# Headphone_Amp.net
KiCad netlist of a schematic drawn in EAGLE
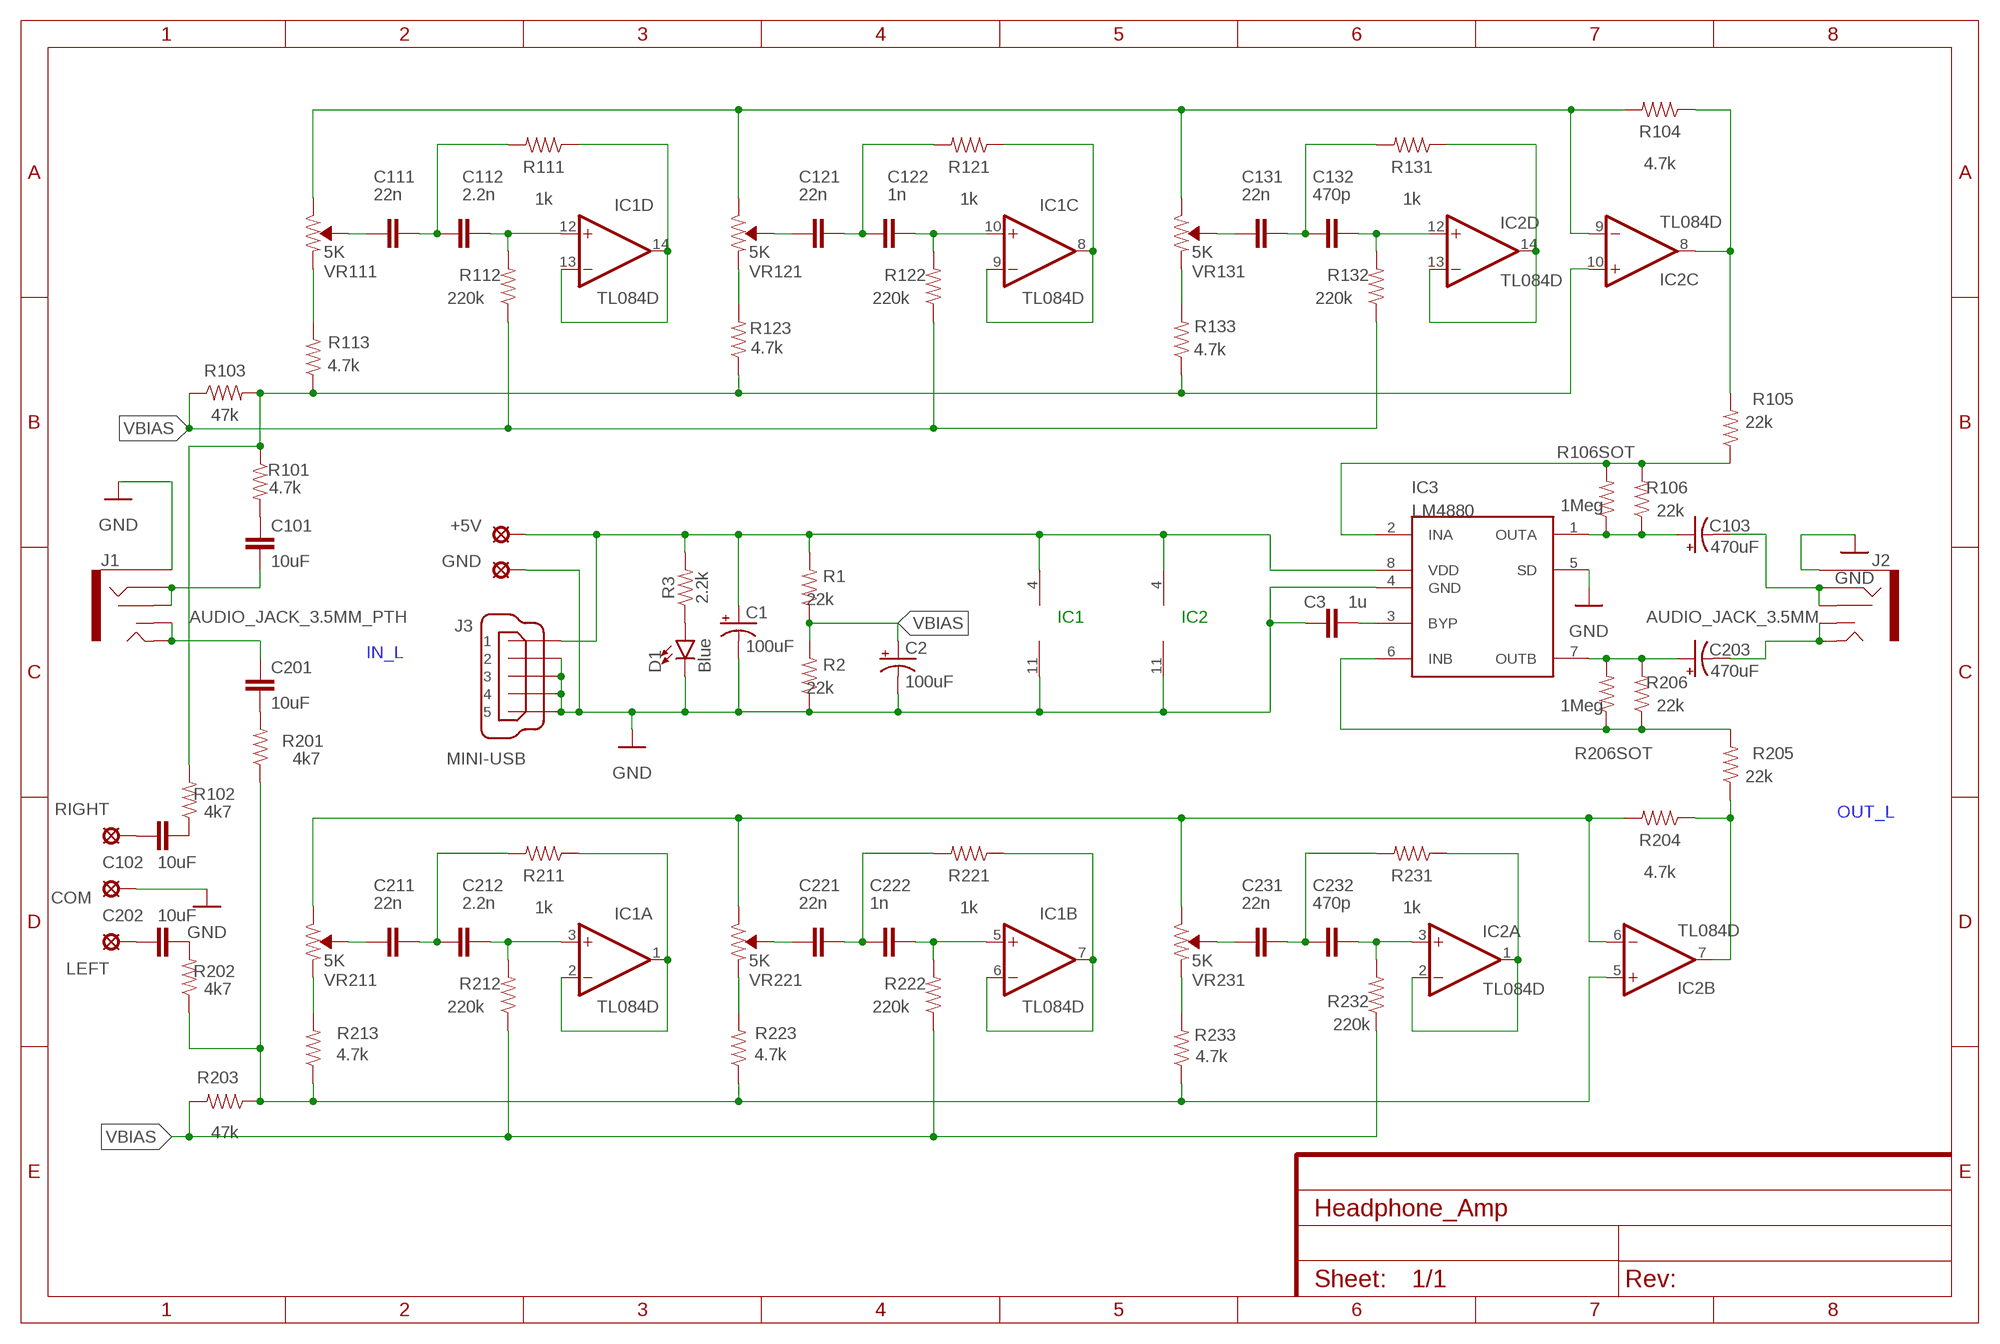
[diagram p0: schematic, sheet 1]

(export (version "E")
  (design (tool "Eeschema 10.0.6"))
  (components
    (comp (ref "+5V")
      (value "SE14")
      (footprint "eagle-import:SE14")
      (fields (field (name "SPICEMODEL") "PwrPlus") (field (name "SPICEPREFIX") "X"))
      (libsource (lib "eagle-import") (part "SE14"))
    )
    (comp (ref "C1")
      (value "100uF")
      (footprint "eagle-import:EIA7343")
      (fields (field (name "SPICEPREFIX") "C"))
      (libsource (lib "eagle-import") (part "100UF-POLAR-EIA7343-16V-10%(TANT)"))
    )
    (comp (ref "C2")
      (value "100uF")
      (footprint "eagle-import:EIA7343")
      (fields (field (name "SPICEPREFIX") "C"))
      (libsource (lib "eagle-import") (part "100UF-POLAR-EIA7343-16V-10%(TANT)"))
    )
    (comp (ref "C3")
      (value "1u")
      (footprint "eagle-import:0603")
      (fields (field (name "SPICEPREFIX") "C"))
      (libsource (lib "eagle-import") (part "0.1UF-0603-25V-5%"))
    )
    (comp (ref "C101")
      (value "10uF")
      (footprint "eagle-import:0805")
      (fields (field (name "SPICEPREFIX") "C"))
      (libsource (lib "eagle-import") (part "10UF-0805-10V-10%"))
    )
    (comp (ref "C102")
      (value "10uF")
      (footprint "eagle-import:0805")
      (fields (field (name "SPICEPREFIX") "C"))
      (libsource (lib "eagle-import") (part "10UF-0805-10V-10%"))
    )
    (comp (ref "C103")
      (value "470uF")
      (footprint "eagle-import:EIA7343")
      (fields (field (name "SPICEPREFIX") "C"))
      (libsource (lib "eagle-import") (part "100UF-POLAR-EIA7343-16V-10%(TANT)"))
    )
    (comp (ref "C111")
      (value "22n")
      (footprint "eagle-import:0603")
      (fields (field (name "SPICEPREFIX") "C"))
      (libsource (lib "eagle-import") (part "0.1UF-0603-25V-5%"))
    )
    (comp (ref "C112")
      (value "2.2n")
      (footprint "eagle-import:0603")
      (fields (field (name "SPICEPREFIX") "C"))
      (libsource (lib "eagle-import") (part "0.1UF-0603-25V-5%"))
    )
    (comp (ref "C121")
      (value "22n")
      (footprint "eagle-import:0603")
      (fields (field (name "SPICEPREFIX") "C"))
      (libsource (lib "eagle-import") (part "0.1UF-0603-25V-5%"))
    )
    (comp (ref "C122")
      (value "1n")
      (footprint "eagle-import:0603")
      (fields (field (name "SPICEPREFIX") "C"))
      (libsource (lib "eagle-import") (part "0.1UF-0603-25V-5%"))
    )
    (comp (ref "C131")
      (value "22n")
      (footprint "eagle-import:0603")
      (fields (field (name "SPICEPREFIX") "C"))
      (libsource (lib "eagle-import") (part "0.1UF-0603-25V-5%"))
    )
    (comp (ref "C132")
      (value "470p")
      (footprint "eagle-import:0603")
      (fields (field (name "SPICEPREFIX") "C"))
      (libsource (lib "eagle-import") (part "0.1UF-0603-25V-5%"))
    )
    (comp (ref "C201")
      (value "10uF")
      (footprint "eagle-import:0805")
      (fields (field (name "SPICEPREFIX") "C"))
      (libsource (lib "eagle-import") (part "10UF-0805-10V-10%"))
    )
    (comp (ref "C202")
      (value "10uF")
      (footprint "eagle-import:0805")
      (fields (field (name "SPICEPREFIX") "C"))
      (libsource (lib "eagle-import") (part "10UF-0805-10V-10%"))
    )
    (comp (ref "C203")
      (value "470uF")
      (footprint "eagle-import:EIA7343")
      (fields (field (name "SPICEPREFIX") "C"))
      (libsource (lib "eagle-import") (part "100UF-POLAR-EIA7343-16V-10%(TANT)"))
    )
    (comp (ref "C211")
      (value "22n")
      (footprint "eagle-import:0603")
      (fields (field (name "SPICEPREFIX") "C"))
      (libsource (lib "eagle-import") (part "0.1UF-0603-25V-5%"))
    )
    (comp (ref "C212")
      (value "2.2n")
      (footprint "eagle-import:0603")
      (fields (field (name "SPICEPREFIX") "C"))
      (libsource (lib "eagle-import") (part "0.1UF-0603-25V-5%"))
    )
    (comp (ref "C221")
      (value "22n")
      (footprint "eagle-import:0603")
      (fields (field (name "SPICEPREFIX") "C"))
      (libsource (lib "eagle-import") (part "0.1UF-0603-25V-5%"))
    )
    (comp (ref "C222")
      (value "1n")
      (footprint "eagle-import:0603")
      (fields (field (name "SPICEPREFIX") "C"))
      (libsource (lib "eagle-import") (part "0.1UF-0603-25V-5%"))
    )
    (comp (ref "C231")
      (value "22n")
      (footprint "eagle-import:0603")
      (fields (field (name "SPICEPREFIX") "C"))
      (libsource (lib "eagle-import") (part "0.1UF-0603-25V-5%"))
    )
    (comp (ref "C232")
      (value "470p")
      (footprint "eagle-import:0603")
      (fields (field (name "SPICEPREFIX") "C"))
      (libsource (lib "eagle-import") (part "0.1UF-0603-25V-5%"))
    )
    (comp (ref "COM")
      (value "SE14")
      (footprint "eagle-import:SE14")
      (fields (field (name "SPICEMODEL") "PwrMinus") (field (name "SPICEPREFIX") "X"))
      (libsource (lib "eagle-import") (part "SE14"))
    )
    (comp (ref "D1")
      (value "Blue")
      (footprint "eagle-import:LED_3MM")
      (fields (field (name "SPICEMODEL") "DMOD") (field (name "SPICEPREFIX") "D"))
      (libsource (lib "eagle-import") (part "LED3MM"))
    )
    (comp (ref "GND")
      (value "SE14")
      (footprint "eagle-import:SE14")
      (fields (field (name "SPICEMODEL") "PwrMinus") (field (name "SPICEPREFIX") "X"))
      (libsource (lib "eagle-import") (part "SE14"))
    )
    (comp (ref "IC1")
      (value "TL084D")
      (footprint "eagle-import:SO14")
      (fields (field (name "SPICEMODEL") "TL084x4") (field (name "SPICEPREFIX") "X"))
      (libsource (lib "eagle-import") (part "TL084D"))
    )
    (comp (ref "IC2")
      (value "TL084D")
      (footprint "eagle-import:SO14")
      (fields (field (name "SPICEMODEL") "TL084x4") (field (name "SPICEPREFIX") "X"))
      (libsource (lib "eagle-import") (part "TL084D"))
    )
    (comp (ref "IC3")
      (value "LM4880")
      (footprint "eagle-import:SO08")
      (fields
        (field (name "MF") "Texas Instruments")
        (field (name "SPICEMODEL") "Fake_LM4880")
        (field (name "SPICEPREFIX") "X")
      )
      (libsource (lib "eagle-import") (part "LM4880"))
    )
    (comp (ref "J1")
      (value "AUDIO_JACK_3.5MM_PTH")
      (footprint "eagle-import:AUDIO-JACK")
      (fields (field (name "SPICEMODEL") "StereoIn") (field (name "SPICEPREFIX") "X"))
      (libsource (lib "eagle-import") (part "AUDIO_JACK_3.5MM_PTH"))
    )
    (comp (ref "J2")
      (value "AUDIO_JACK_3.5MM")
      (footprint "eagle-import:AUDIO-JACK")
      (fields (field (name "SPICEMODEL") "StereoOut") (field (name "SPICEPREFIX") "X"))
      (libsource (lib "eagle-import") (part "AUDIO_JACK_3.5MM_PTH"))
    )
    (comp (ref "J3")
      (value "MINI-USB")
      (footprint "eagle-import:UX60A-MB-5ST")
      (fields (field (name "SPICEMODEL") "USBSupply") (field (name "SPICEPREFIX") "X"))
      (libsource (lib "eagle-import") (part "MINI-USB-UX60A-MB-5ST"))
    )
    (comp (ref "LEFT")
      (value "SE14")
      (footprint "eagle-import:SE14")
      (fields (field (name "SPICEMODEL") "AudioIn") (field (name "SPICEPREFIX") "X"))
      (libsource (lib "eagle-import") (part "SE14"))
    )
    (comp (ref "R1")
      (value "22k")
      (footprint "eagle-import:0603")
      (fields (field (name "SPICEPREFIX") "R"))
      (libsource (lib "eagle-import") (part "RESISTOR0603"))
    )
    (comp (ref "R2")
      (value "22k")
      (footprint "eagle-import:0603")
      (fields (field (name "SPICEPREFIX") "R"))
      (libsource (lib "eagle-import") (part "RESISTOR0603"))
    )
    (comp (ref "R3")
      (value "2.2k")
      (footprint "eagle-import:0603")
      (fields (field (name "SPICEPREFIX") "R"))
      (libsource (lib "eagle-import") (part "2.2KOHM-0603-1/10W-1%"))
    )
    (comp (ref "R101")
      (value "4.7k")
      (footprint "eagle-import:0603")
      (fields (field (name "SPICEPREFIX") "R"))
      (libsource (lib "eagle-import") (part "RESISTOR0603"))
    )
    (comp (ref "R102")
      (value "4k7")
      (footprint "eagle-import:0603")
      (fields (field (name "SPICEPREFIX") "R"))
      (libsource (lib "eagle-import") (part "RESISTOR0603"))
    )
    (comp (ref "R103")
      (value "47k")
      (footprint "eagle-import:0603")
      (fields (field (name "SPICEPREFIX") "R"))
      (libsource (lib "eagle-import") (part "RESISTOR0603"))
    )
    (comp (ref "R104")
      (value "4.7k")
      (footprint "eagle-import:0603")
      (fields (field (name "SPICEPREFIX") "R"))
      (libsource (lib "eagle-import") (part "RESISTOR0603"))
    )
    (comp (ref "R105")
      (value "22k")
      (footprint "eagle-import:0603")
      (fields (field (name "SPICEPREFIX") "R"))
      (libsource (lib "eagle-import") (part "RESISTOR0603"))
    )
    (comp (ref "R106")
      (value "22k")
      (footprint "eagle-import:0603")
      (fields (field (name "SPICEPREFIX") "R"))
      (libsource (lib "eagle-import") (part "RESISTOR0603"))
    )
    (comp (ref "R106SOT")
      (value "1Meg")
      (footprint "eagle-import:AXIAL-0.3")
      (fields (field (name "SPICEPREFIX") "R"))
      (libsource (lib "eagle-import") (part "RESISTORAXIAL-0.3"))
    )
    (comp (ref "R111")
      (value "1k")
      (footprint "eagle-import:0603")
      (fields (field (name "SPICEPREFIX") "R"))
      (libsource (lib "eagle-import") (part "RESISTOR0603"))
    )
    (comp (ref "R112")
      (value "220k")
      (footprint "eagle-import:0603")
      (fields (field (name "SPICEPREFIX") "R"))
      (libsource (lib "eagle-import") (part "RESISTOR0603"))
    )
    (comp (ref "R113")
      (value "4.7k")
      (footprint "eagle-import:0603")
      (fields (field (name "SPICEPREFIX") "R"))
      (libsource (lib "eagle-import") (part "4.7KOHM-0603-1/10W-1%"))
    )
    (comp (ref "R121")
      (value "1k")
      (footprint "eagle-import:0603")
      (fields (field (name "SPICEPREFIX") "R"))
      (libsource (lib "eagle-import") (part "RESISTOR0603"))
    )
    (comp (ref "R122")
      (value "220k")
      (footprint "eagle-import:0603")
      (fields (field (name "SPICEPREFIX") "R"))
      (libsource (lib "eagle-import") (part "RESISTOR0603"))
    )
    (comp (ref "R123")
      (value "4.7k")
      (footprint "eagle-import:0603")
      (fields (field (name "SPICEPREFIX") "R"))
      (libsource (lib "eagle-import") (part "4.7KOHM-0603-1/10W-1%"))
    )
    (comp (ref "R131")
      (value "1k")
      (footprint "eagle-import:0603")
      (fields (field (name "SPICEPREFIX") "R"))
      (libsource (lib "eagle-import") (part "RESISTOR0603"))
    )
    (comp (ref "R132")
      (value "220k")
      (footprint "eagle-import:0603")
      (fields (field (name "SPICEPREFIX") "R"))
      (libsource (lib "eagle-import") (part "RESISTOR0603"))
    )
    (comp (ref "R133")
      (value "4.7k")
      (footprint "eagle-import:0603")
      (fields (field (name "SPICEPREFIX") "R"))
      (libsource (lib "eagle-import") (part "4.7KOHM-0603-1/10W-1%"))
    )
    (comp (ref "R201")
      (value "4k7")
      (footprint "eagle-import:0603")
      (fields (field (name "SPICEPREFIX") "R"))
      (libsource (lib "eagle-import") (part "RESISTOR0603"))
    )
    (comp (ref "R202")
      (value "4k7")
      (footprint "eagle-import:0603")
      (fields (field (name "SPICEPREFIX") "R"))
      (libsource (lib "eagle-import") (part "RESISTOR0603"))
    )
    (comp (ref "R203")
      (value "47k")
      (footprint "eagle-import:0603")
      (fields (field (name "SPICEPREFIX") "R"))
      (libsource (lib "eagle-import") (part "RESISTOR0603"))
    )
    (comp (ref "R204")
      (value "4.7k")
      (footprint "eagle-import:0603")
      (fields (field (name "SPICEPREFIX") "R"))
      (libsource (lib "eagle-import") (part "RESISTOR0603"))
    )
    (comp (ref "R205")
      (value "22k")
      (footprint "eagle-import:0603")
      (fields (field (name "SPICEPREFIX") "R"))
      (libsource (lib "eagle-import") (part "RESISTOR0603"))
    )
    (comp (ref "R206")
      (value "22k")
      (footprint "eagle-import:0603")
      (fields (field (name "SPICEPREFIX") "R"))
      (libsource (lib "eagle-import") (part "RESISTOR0603"))
    )
    (comp (ref "R206SOT")
      (value "1Meg")
      (footprint "eagle-import:AXIAL-0.3")
      (fields (field (name "SPICEPREFIX") "R"))
      (libsource (lib "eagle-import") (part "RESISTORAXIAL-0.3"))
    )
    (comp (ref "R211")
      (value "1k")
      (footprint "eagle-import:0603")
      (fields (field (name "SPICEPREFIX") "R"))
      (libsource (lib "eagle-import") (part "RESISTOR0603"))
    )
    (comp (ref "R212")
      (value "220k")
      (footprint "eagle-import:0603")
      (fields (field (name "SPICEPREFIX") "R"))
      (libsource (lib "eagle-import") (part "RESISTOR0603"))
    )
    (comp (ref "R213")
      (value "4.7k")
      (footprint "eagle-import:0603")
      (fields (field (name "SPICEPREFIX") "R"))
      (libsource (lib "eagle-import") (part "4.7KOHM-0603-1/10W-1%"))
    )
    (comp (ref "R221")
      (value "1k")
      (footprint "eagle-import:0603")
      (fields (field (name "SPICEPREFIX") "R"))
      (libsource (lib "eagle-import") (part "RESISTOR0603"))
    )
    (comp (ref "R222")
      (value "220k")
      (footprint "eagle-import:0603")
      (fields (field (name "SPICEPREFIX") "R"))
      (libsource (lib "eagle-import") (part "RESISTOR0603"))
    )
    (comp (ref "R223")
      (value "4.7k")
      (footprint "eagle-import:0603")
      (fields (field (name "SPICEPREFIX") "R"))
      (libsource (lib "eagle-import") (part "4.7KOHM-0603-1/10W-1%"))
    )
    (comp (ref "R231")
      (value "1k")
      (footprint "eagle-import:0603")
      (fields (field (name "SPICEPREFIX") "R"))
      (libsource (lib "eagle-import") (part "RESISTOR0603"))
    )
    (comp (ref "R232")
      (value "220k")
      (footprint "eagle-import:0603")
      (fields (field (name "SPICEPREFIX") "R"))
      (libsource (lib "eagle-import") (part "RESISTOR0603"))
    )
    (comp (ref "R233")
      (value "4.7k")
      (footprint "eagle-import:0603")
      (fields (field (name "SPICEPREFIX") "R"))
      (libsource (lib "eagle-import") (part "4.7KOHM-0603-1/10W-1%"))
    )
    (comp (ref "RIGHT")
      (value "SE14")
      (footprint "eagle-import:SE14")
      (fields (field (name "SPICEMODEL") "AudioIn") (field (name "SPICEPREFIX") "X"))
      (libsource (lib "eagle-import") (part "SE14"))
    )
    (comp (ref "VR111")
      (value "5K")
      (footprint "eagle-import:TRIMPOT-PTH-3362P")
      (fields (field (name "SPICEMODEL") "POT_VR111") (field (name "SPICEPREFIX") "X"))
      (libsource (lib "eagle-import") (part "TRIMPOTTRIMPOT-PTH-3362P"))
    )
    (comp (ref "VR121")
      (value "5K")
      (footprint "eagle-import:TRIMPOT-PTH-3362P")
      (fields (field (name "SPICEMODEL") "POT_VR121") (field (name "SPICEPREFIX") "X"))
      (libsource (lib "eagle-import") (part "TRIMPOTTRIMPOT-PTH-3362P"))
    )
    (comp (ref "VR131")
      (value "5K")
      (footprint "eagle-import:TRIMPOT-PTH-3362P")
      (fields (field (name "SPICEMODEL") "POT_VR131") (field (name "SPICEPREFIX") "X"))
      (libsource (lib "eagle-import") (part "TRIMPOTTRIMPOT-PTH-3362P"))
    )
    (comp (ref "VR211")
      (value "5K")
      (footprint "eagle-import:TRIMPOT-PTH-3362P")
      (fields (field (name "SPICEMODEL") "POT_VR111") (field (name "SPICEPREFIX") "X"))
      (libsource (lib "eagle-import") (part "TRIMPOTTRIMPOT-PTH-3362P"))
    )
    (comp (ref "VR221")
      (value "5K")
      (footprint "eagle-import:TRIMPOT-PTH-3362P")
      (fields (field (name "SPICEMODEL") "POT_VR121") (field (name "SPICEPREFIX") "X"))
      (libsource (lib "eagle-import") (part "TRIMPOTTRIMPOT-PTH-3362P"))
    )
    (comp (ref "VR231")
      (value "5K")
      (footprint "eagle-import:TRIMPOT-PTH-3362P")
      (fields (field (name "SPICEMODEL") "POT_VR131") (field (name "SPICEPREFIX") "X"))
      (libsource (lib "eagle-import") (part "TRIMPOTTRIMPOT-PTH-3362P"))
    )
  )
  (nets
    (net (code "1") (name "GND") (class "Default")
      (node (ref "C1") (pin "C") (pinfunction "-_C") (pintype "passive"))
      (node (ref "C2") (pin "C") (pinfunction "-_C") (pintype "passive"))
      (node (ref "C3") (pin "1") (pinfunction "1_1") (pintype "passive"))
      (node (ref "COM") (pin "MP") (pinfunction "MP_MP") (pintype "passive"))
      (node (ref "D1") (pin "K") (pinfunction "C_K") (pintype "passive"))
      (node (ref "GND") (pin "MP") (pinfunction "MP_MP") (pintype "passive"))
      (node (ref "IC1") (pin "11") (pinfunction "V-_11") (pintype "power_in"))
      (node (ref "IC2") (pin "11") (pinfunction "V-_11") (pintype "power_in"))
      (node (ref "IC3") (pin "4") (pinfunction "GND_4") (pintype "power_in"))
      (node (ref "IC3") (pin "5") (pinfunction "SD_5") (pintype "bidirectional"))
      (node (ref "J1") (pin "SLEEVE") (pinfunction "SLEEVE_SLEEVE") (pintype "bidirectional"))
      (node (ref "J2") (pin "SLEEVE") (pinfunction "SLEEVE_SLEEVE") (pintype "bidirectional"))
      (node (ref "J3") (pin "2") (pinfunction "2_2") (pintype "input"))
      (node (ref "J3") (pin "3") (pinfunction "3_3") (pintype "input"))
      (node (ref "J3") (pin "4") (pinfunction "4_4") (pintype "input"))
      (node (ref "J3") (pin "5") (pinfunction "5_5") (pintype "input"))
      (node (ref "R2") (pin "1") (pinfunction "1_1") (pintype "passive"))
    )
    (net (code "2") (name "Net-(C1-+)") (class "Default")
      (node (ref "+5V") (pin "MP") (pinfunction "MP_MP") (pintype "passive"))
      (node (ref "C1") (pin "A") (pinfunction "+_A") (pintype "passive"))
      (node (ref "IC1") (pin "4") (pinfunction "V+_4") (pintype "power_in"))
      (node (ref "IC2") (pin "4") (pinfunction "V+_4") (pintype "power_in"))
      (node (ref "IC3") (pin "8") (pinfunction "VDD_8") (pintype "power_in"))
      (node (ref "J3") (pin "1") (pinfunction "1_1") (pintype "input"))
      (node (ref "R1") (pin "2") (pinfunction "2_2") (pintype "passive"))
      (node (ref "R3") (pin "2") (pinfunction "2_2") (pintype "passive"))
    )
    (net (code "3") (name "Net-(C101-Pad1)") (class "Default")
      (node (ref "C101") (pin "1") (pinfunction "1_1") (pintype "passive"))
      (node (ref "R101") (pin "2") (pinfunction "2_2") (pintype "passive"))
    )
    (net (code "4") (name "Net-(C101-Pad2)") (class "Default")
      (node (ref "C101") (pin "2") (pinfunction "2_2") (pintype "passive"))
      (node (ref "J1") (pin "RING") (pinfunction "RING_RING") (pintype "bidirectional"))
      (node (ref "J1") (pin "RSH") (pinfunction "RSH_RSH") (pintype "bidirectional"))
    )
    (net (code "5") (name "Net-(C102-Pad1)") (class "Default")
      (node (ref "C102") (pin "1") (pinfunction "1_1") (pintype "passive"))
      (node (ref "RIGHT") (pin "MP") (pinfunction "MP_MP") (pintype "passive"))
    )
    (net (code "6") (name "Net-(C102-Pad2)") (class "Default")
      (node (ref "C102") (pin "2") (pinfunction "2_2") (pintype "passive"))
      (node (ref "R102") (pin "1") (pinfunction "1_1") (pintype "passive"))
    )
    (net (code "7") (name "Net-(C103-+)") (class "Default")
      (node (ref "C103") (pin "A") (pinfunction "+_A") (pintype "passive"))
      (node (ref "IC3") (pin "1") (pinfunction "OUTA_1") (pintype "output"))
      (node (ref "R106") (pin "1") (pinfunction "1_1") (pintype "passive"))
      (node (ref "R106SOT") (pin "P$1") (pinfunction "1_P$1") (pintype "passive"))
    )
    (net (code "8") (name "Net-(C103--)") (class "Default")
      (node (ref "C103") (pin "C") (pinfunction "-_C") (pintype "passive"))
      (node (ref "J2") (pin "RING") (pinfunction "RING_RING") (pintype "bidirectional"))
      (node (ref "J2") (pin "RSH") (pinfunction "RSH_RSH") (pintype "bidirectional"))
    )
    (net (code "9") (name "Net-(C111-Pad2)") (class "Default")
      (node (ref "C111") (pin "2") (pinfunction "2_2") (pintype "passive"))
      (node (ref "C112") (pin "1") (pinfunction "1_1") (pintype "passive"))
      (node (ref "R111") (pin "2") (pinfunction "2_2") (pintype "passive"))
    )
    (net (code "10") (name "Net-(C121-Pad2)") (class "Default")
      (node (ref "C121") (pin "2") (pinfunction "2_2") (pintype "passive"))
      (node (ref "C122") (pin "1") (pinfunction "1_1") (pintype "passive"))
      (node (ref "R121") (pin "2") (pinfunction "2_2") (pintype "passive"))
    )
    (net (code "11") (name "Net-(C131-Pad2)") (class "Default")
      (node (ref "C131") (pin "2") (pinfunction "2_2") (pintype "passive"))
      (node (ref "C132") (pin "1") (pinfunction "1_1") (pintype "passive"))
      (node (ref "R131") (pin "2") (pinfunction "2_2") (pintype "passive"))
    )
    (net (code "12") (name "Net-(C201-Pad1)") (class "Default")
      (node (ref "C201") (pin "1") (pinfunction "1_1") (pintype "passive"))
      (node (ref "J1") (pin "TIP") (pinfunction "TIP_TIP") (pintype "bidirectional"))
      (node (ref "J1") (pin "TSH") (pinfunction "TSH_TSH") (pintype "bidirectional"))
    )
    (net (code "13") (name "Net-(C201-Pad2)") (class "Default")
      (node (ref "C201") (pin "2") (pinfunction "2_2") (pintype "passive"))
      (node (ref "R201") (pin "2") (pinfunction "2_2") (pintype "passive"))
    )
    (net (code "14") (name "Net-(C202-Pad1)") (class "Default")
      (node (ref "C202") (pin "1") (pinfunction "1_1") (pintype "passive"))
      (node (ref "LEFT") (pin "MP") (pinfunction "MP_MP") (pintype "passive"))
    )
    (net (code "15") (name "Net-(C202-Pad2)") (class "Default")
      (node (ref "C202") (pin "2") (pinfunction "2_2") (pintype "passive"))
      (node (ref "R202") (pin "2") (pinfunction "2_2") (pintype "passive"))
    )
    (net (code "16") (name "Net-(C203-+)") (class "Default")
      (node (ref "C203") (pin "A") (pinfunction "+_A") (pintype "passive"))
      (node (ref "IC3") (pin "7") (pinfunction "OUTB_7") (pintype "output"))
      (node (ref "R206") (pin "2") (pinfunction "2_2") (pintype "passive"))
      (node (ref "R206SOT") (pin "P$2") (pinfunction "2_P$2") (pintype "passive"))
    )
    (net (code "17") (name "Net-(C203--)") (class "Default")
      (node (ref "C203") (pin "C") (pinfunction "-_C") (pintype "passive"))
      (node (ref "J2") (pin "TIP") (pinfunction "TIP_TIP") (pintype "bidirectional"))
      (node (ref "J2") (pin "TSH") (pinfunction "TSH_TSH") (pintype "bidirectional"))
    )
    (net (code "18") (name "Net-(C211-Pad2)") (class "Default")
      (node (ref "C211") (pin "2") (pinfunction "2_2") (pintype "passive"))
      (node (ref "C212") (pin "1") (pinfunction "1_1") (pintype "passive"))
      (node (ref "R211") (pin "2") (pinfunction "2_2") (pintype "passive"))
    )
    (net (code "19") (name "Net-(C221-Pad2)") (class "Default")
      (node (ref "C221") (pin "2") (pinfunction "2_2") (pintype "passive"))
      (node (ref "C222") (pin "1") (pinfunction "1_1") (pintype "passive"))
      (node (ref "R221") (pin "2") (pinfunction "2_2") (pintype "passive"))
    )
    (net (code "20") (name "Net-(C231-Pad2)") (class "Default")
      (node (ref "C231") (pin "2") (pinfunction "2_2") (pintype "passive"))
      (node (ref "C232") (pin "1") (pinfunction "1_1") (pintype "passive"))
      (node (ref "R231") (pin "2") (pinfunction "2_2") (pintype "passive"))
    )
    (net (code "21") (name "Net-(D1-PadA)") (class "Default")
      (node (ref "D1") (pin "A") (pinfunction "A_A") (pintype "passive"))
      (node (ref "R3") (pin "1") (pinfunction "1_1") (pintype "passive"))
    )
    (net (code "22") (name "Net-(IC1A-+IN)") (class "Default")
      (node (ref "C212") (pin "2") (pinfunction "2_2") (pintype "passive"))
      (node (ref "IC1") (pin "3") (pinfunction "+IN_3") (pintype "input"))
      (node (ref "R212") (pin "2") (pinfunction "2_2") (pintype "passive"))
    )
    (net (code "23") (name "Net-(IC1A--IN)") (class "Default")
      (node (ref "IC1") (pin "1") (pinfunction "OUT_1") (pintype "output"))
      (node (ref "IC1") (pin "2") (pinfunction "-IN_2") (pintype "input"))
      (node (ref "R211") (pin "1") (pinfunction "1_1") (pintype "passive"))
    )
    (net (code "24") (name "Net-(IC1B-+IN)") (class "Default")
      (node (ref "C222") (pin "2") (pinfunction "2_2") (pintype "passive"))
      (node (ref "IC1") (pin "5") (pinfunction "+IN_5") (pintype "input"))
      (node (ref "R222") (pin "2") (pinfunction "2_2") (pintype "passive"))
    )
    (net (code "25") (name "Net-(IC1B--IN)") (class "Default")
      (node (ref "IC1") (pin "6") (pinfunction "-IN_6") (pintype "input"))
      (node (ref "IC1") (pin "7") (pinfunction "OUT_7") (pintype "output"))
      (node (ref "R221") (pin "1") (pinfunction "1_1") (pintype "passive"))
    )
    (net (code "26") (name "Net-(IC1C-+IN)") (class "Default")
      (node (ref "C122") (pin "2") (pinfunction "2_2") (pintype "passive"))
      (node (ref "IC1") (pin "10") (pinfunction "+IN_10") (pintype "input"))
      (node (ref "R122") (pin "2") (pinfunction "2_2") (pintype "passive"))
    )
    (net (code "27") (name "Net-(IC1C--IN)") (class "Default")
      (node (ref "IC1") (pin "8") (pinfunction "OUT_8") (pintype "output"))
      (node (ref "IC1") (pin "9") (pinfunction "-IN_9") (pintype "input"))
      (node (ref "R121") (pin "1") (pinfunction "1_1") (pintype "passive"))
    )
    (net (code "28") (name "Net-(IC1D-+IN)") (class "Default")
      (node (ref "C112") (pin "2") (pinfunction "2_2") (pintype "passive"))
      (node (ref "IC1") (pin "12") (pinfunction "+IN_12") (pintype "input"))
      (node (ref "R112") (pin "2") (pinfunction "2_2") (pintype "passive"))
    )
    (net (code "29") (name "Net-(IC1D--IN)") (class "Default")
      (node (ref "IC1") (pin "13") (pinfunction "-IN_13") (pintype "input"))
      (node (ref "IC1") (pin "14") (pinfunction "OUT_14") (pintype "output"))
      (node (ref "R111") (pin "1") (pinfunction "1_1") (pintype "passive"))
    )
    (net (code "30") (name "Net-(IC2A-+IN)") (class "Default")
      (node (ref "C232") (pin "2") (pinfunction "2_2") (pintype "passive"))
      (node (ref "IC2") (pin "3") (pinfunction "+IN_3") (pintype "input"))
      (node (ref "R232") (pin "2") (pinfunction "2_2") (pintype "passive"))
    )
    (net (code "31") (name "Net-(IC2A--IN)") (class "Default")
      (node (ref "IC2") (pin "1") (pinfunction "OUT_1") (pintype "output"))
      (node (ref "IC2") (pin "2") (pinfunction "-IN_2") (pintype "input"))
      (node (ref "R231") (pin "1") (pinfunction "1_1") (pintype "passive"))
    )
    (net (code "32") (name "Net-(IC2B-+IN)") (class "Default")
      (node (ref "IC2") (pin "5") (pinfunction "+IN_5") (pintype "input"))
      (node (ref "R201") (pin "1") (pinfunction "1_1") (pintype "passive"))
      (node (ref "R202") (pin "1") (pinfunction "1_1") (pintype "passive"))
      (node (ref "R203") (pin "1") (pinfunction "1_1") (pintype "passive"))
      (node (ref "R213") (pin "1") (pinfunction "1_1") (pintype "passive"))
      (node (ref "R223") (pin "1") (pinfunction "1_1") (pintype "passive"))
      (node (ref "R233") (pin "1") (pinfunction "1_1") (pintype "passive"))
    )
    (net (code "33") (name "Net-(IC2B--IN)") (class "Default")
      (node (ref "IC2") (pin "6") (pinfunction "-IN_6") (pintype "input"))
      (node (ref "R204") (pin "2") (pinfunction "2_2") (pintype "passive"))
      (node (ref "VR211") (pin "3") (pinfunction "CW_3") (pintype "passive"))
      (node (ref "VR221") (pin "3") (pinfunction "CW_3") (pintype "passive"))
      (node (ref "VR231") (pin "3") (pinfunction "CW_3") (pintype "passive"))
    )
    (net (code "34") (name "Net-(IC2B-OUT)") (class "Default")
      (node (ref "IC2") (pin "7") (pinfunction "OUT_7") (pintype "output"))
      (node (ref "R204") (pin "1") (pinfunction "1_1") (pintype "passive"))
      (node (ref "R205") (pin "1") (pinfunction "1_1") (pintype "passive"))
    )
    (net (code "35") (name "Net-(IC2C-+IN)") (class "Default")
      (node (ref "IC2") (pin "10") (pinfunction "+IN_10") (pintype "input"))
      (node (ref "R101") (pin "1") (pinfunction "1_1") (pintype "passive"))
      (node (ref "R102") (pin "2") (pinfunction "2_2") (pintype "passive"))
      (node (ref "R103") (pin "2") (pinfunction "2_2") (pintype "passive"))
      (node (ref "R113") (pin "1") (pinfunction "1_1") (pintype "passive"))
      (node (ref "R123") (pin "1") (pinfunction "1_1") (pintype "passive"))
      (node (ref "R133") (pin "1") (pinfunction "1_1") (pintype "passive"))
    )
    (net (code "36") (name "Net-(IC2C--IN)") (class "Default")
      (node (ref "IC2") (pin "9") (pinfunction "-IN_9") (pintype "input"))
      (node (ref "R104") (pin "2") (pinfunction "2_2") (pintype "passive"))
      (node (ref "VR111") (pin "3") (pinfunction "CW_3") (pintype "passive"))
      (node (ref "VR121") (pin "3") (pinfunction "CW_3") (pintype "passive"))
      (node (ref "VR131") (pin "3") (pinfunction "CW_3") (pintype "passive"))
    )
    (net (code "37") (name "Net-(IC2C-OUT)") (class "Default")
      (node (ref "IC2") (pin "8") (pinfunction "OUT_8") (pintype "output"))
      (node (ref "R104") (pin "1") (pinfunction "1_1") (pintype "passive"))
      (node (ref "R105") (pin "2") (pinfunction "2_2") (pintype "passive"))
    )
    (net (code "38") (name "Net-(IC2D-+IN)") (class "Default")
      (node (ref "C132") (pin "2") (pinfunction "2_2") (pintype "passive"))
      (node (ref "IC2") (pin "12") (pinfunction "+IN_12") (pintype "input"))
      (node (ref "R132") (pin "2") (pinfunction "2_2") (pintype "passive"))
    )
    (net (code "39") (name "Net-(IC2D--IN)") (class "Default")
      (node (ref "IC2") (pin "13") (pinfunction "-IN_13") (pintype "input"))
      (node (ref "IC2") (pin "14") (pinfunction "OUT_14") (pintype "output"))
      (node (ref "R131") (pin "1") (pinfunction "1_1") (pintype "passive"))
    )
    (net (code "40") (name "Net-(IC3-BYP)") (class "Default")
      (node (ref "C3") (pin "2") (pinfunction "2_2") (pintype "passive"))
      (node (ref "IC3") (pin "3") (pinfunction "BYP_3") (pintype "bidirectional"))
    )
    (net (code "41") (name "Net-(IC3-INA)") (class "Default")
      (node (ref "IC3") (pin "2") (pinfunction "INA_2") (pintype "input"))
      (node (ref "R105") (pin "1") (pinfunction "1_1") (pintype "passive"))
      (node (ref "R106") (pin "2") (pinfunction "2_2") (pintype "passive"))
      (node (ref "R106SOT") (pin "P$2") (pinfunction "2_P$2") (pintype "passive"))
    )
    (net (code "42") (name "Net-(IC3-INB)") (class "Default")
      (node (ref "IC3") (pin "6") (pinfunction "INB_6") (pintype "input"))
      (node (ref "R205") (pin "2") (pinfunction "2_2") (pintype "passive"))
      (node (ref "R206") (pin "1") (pinfunction "1_1") (pintype "passive"))
      (node (ref "R206SOT") (pin "P$1") (pinfunction "1_P$1") (pintype "passive"))
    )
    (net (code "43") (name "Net-(VR111-CCW)") (class "Default")
      (node (ref "R113") (pin "2") (pinfunction "2_2") (pintype "passive"))
      (node (ref "VR111") (pin "1") (pinfunction "CCW_1") (pintype "passive"))
    )
    (net (code "44") (name "Net-(VR111-WIPER)") (class "Default")
      (node (ref "C111") (pin "1") (pinfunction "1_1") (pintype "passive"))
      (node (ref "VR111") (pin "2") (pinfunction "WIPER_2") (pintype "passive"))
    )
    (net (code "45") (name "Net-(VR121-CCW)") (class "Default")
      (node (ref "R123") (pin "2") (pinfunction "2_2") (pintype "passive"))
      (node (ref "VR121") (pin "1") (pinfunction "CCW_1") (pintype "passive"))
    )
    (net (code "46") (name "Net-(VR121-WIPER)") (class "Default")
      (node (ref "C121") (pin "1") (pinfunction "1_1") (pintype "passive"))
      (node (ref "VR121") (pin "2") (pinfunction "WIPER_2") (pintype "passive"))
    )
    (net (code "47") (name "Net-(VR131-CCW)") (class "Default")
      (node (ref "R133") (pin "2") (pinfunction "2_2") (pintype "passive"))
      (node (ref "VR131") (pin "1") (pinfunction "CCW_1") (pintype "passive"))
    )
    (net (code "48") (name "Net-(VR131-WIPER)") (class "Default")
      (node (ref "C131") (pin "1") (pinfunction "1_1") (pintype "passive"))
      (node (ref "VR131") (pin "2") (pinfunction "WIPER_2") (pintype "passive"))
    )
    (net (code "49") (name "Net-(VR211-CCW)") (class "Default")
      (node (ref "R213") (pin "2") (pinfunction "2_2") (pintype "passive"))
      (node (ref "VR211") (pin "1") (pinfunction "CCW_1") (pintype "passive"))
    )
    (net (code "50") (name "Net-(VR211-WIPER)") (class "Default")
      (node (ref "C211") (pin "1") (pinfunction "1_1") (pintype "passive"))
      (node (ref "VR211") (pin "2") (pinfunction "WIPER_2") (pintype "passive"))
    )
    (net (code "51") (name "Net-(VR221-CCW)") (class "Default")
      (node (ref "R223") (pin "2") (pinfunction "2_2") (pintype "passive"))
      (node (ref "VR221") (pin "1") (pinfunction "CCW_1") (pintype "passive"))
    )
    (net (code "52") (name "Net-(VR221-WIPER)") (class "Default")
      (node (ref "C221") (pin "1") (pinfunction "1_1") (pintype "passive"))
      (node (ref "VR221") (pin "2") (pinfunction "WIPER_2") (pintype "passive"))
    )
    (net (code "53") (name "Net-(VR231-CCW)") (class "Default")
      (node (ref "R233") (pin "2") (pinfunction "2_2") (pintype "passive"))
      (node (ref "VR231") (pin "1") (pinfunction "CCW_1") (pintype "passive"))
    )
    (net (code "54") (name "Net-(VR231-WIPER)") (class "Default")
      (node (ref "C231") (pin "1") (pinfunction "1_1") (pintype "passive"))
      (node (ref "VR231") (pin "2") (pinfunction "WIPER_2") (pintype "passive"))
    )
    (net (code "55") (name "VBIAS") (class "Default")
      (node (ref "C2") (pin "A") (pinfunction "+_A") (pintype "passive"))
      (node (ref "R1") (pin "1") (pinfunction "1_1") (pintype "passive"))
      (node (ref "R103") (pin "1") (pinfunction "1_1") (pintype "passive"))
      (node (ref "R112") (pin "1") (pinfunction "1_1") (pintype "passive"))
      (node (ref "R122") (pin "1") (pinfunction "1_1") (pintype "passive"))
      (node (ref "R132") (pin "1") (pinfunction "1_1") (pintype "passive"))
      (node (ref "R2") (pin "2") (pinfunction "2_2") (pintype "passive"))
      (node (ref "R203") (pin "2") (pinfunction "2_2") (pintype "passive"))
      (node (ref "R212") (pin "1") (pinfunction "1_1") (pintype "passive"))
      (node (ref "R222") (pin "1") (pinfunction "1_1") (pintype "passive"))
      (node (ref "R232") (pin "1") (pinfunction "1_1") (pintype "passive"))
    )
  )
)
